# ESP32.net
KiCad netlist of a schematic drawn in Altium Designer
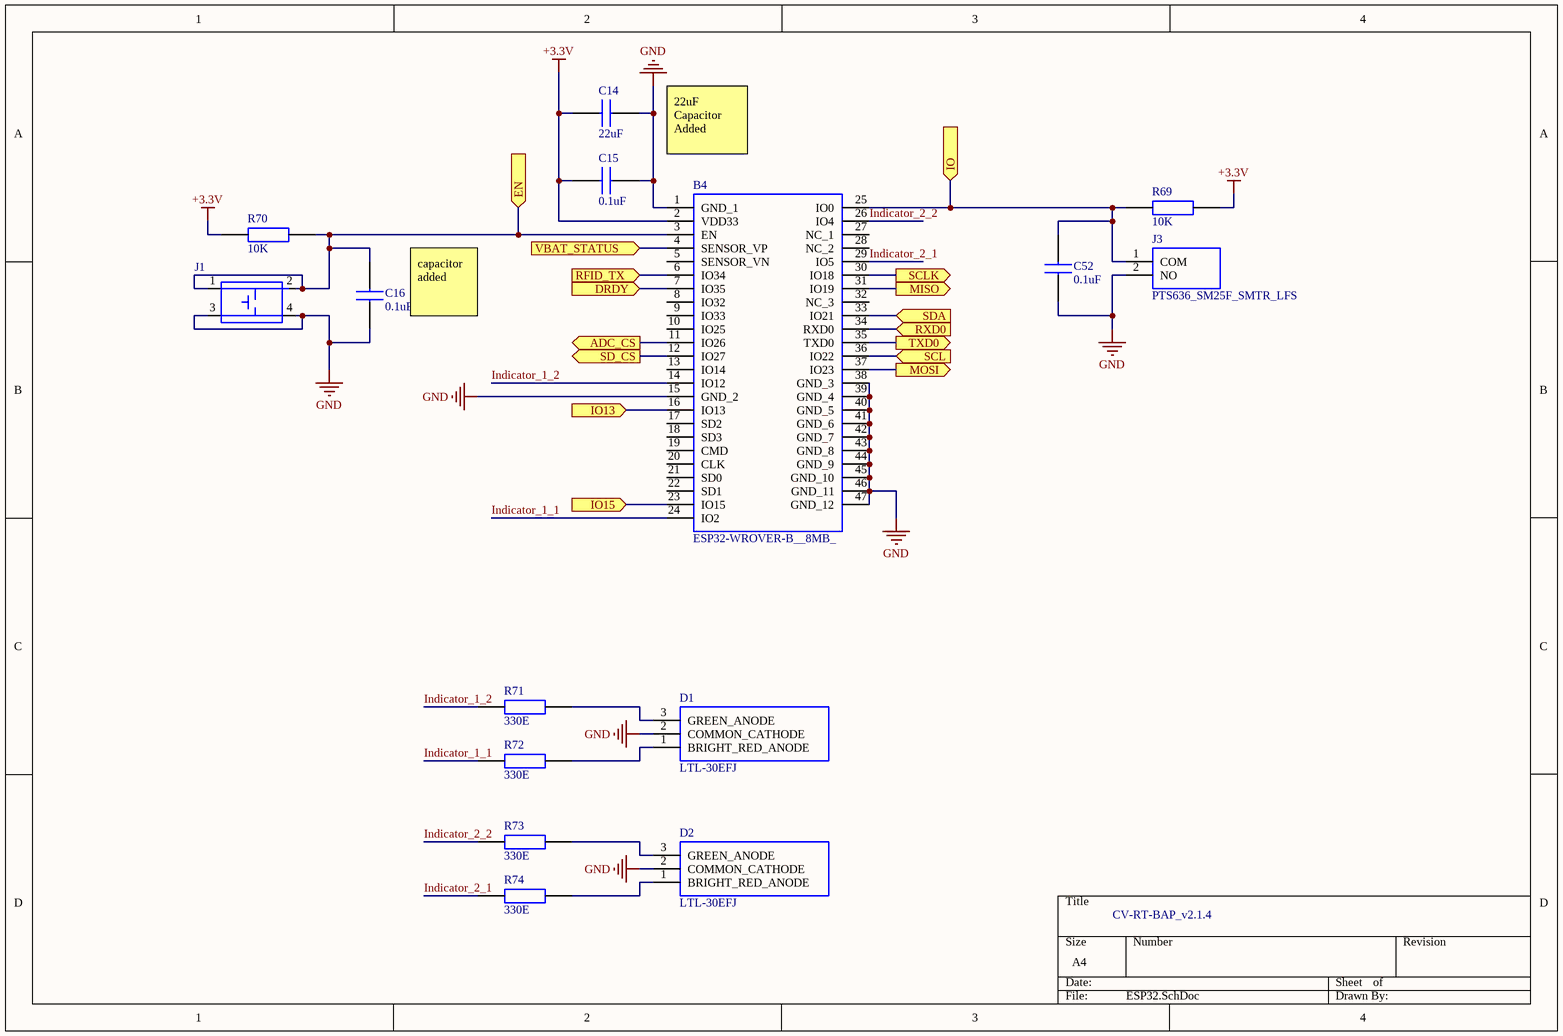
[diagram p0: ESP32.SchDoc]

(export (version "E")
  (design (tool "Eeschema 10.0.6"))
  (components
    (comp (ref "B4")
      (value "ESP32-WROVER-B__8MB_")
      (footprint "ESP32WROVERB8MB")
      (fields
        (field (name "MANUFACTURER_PART_NUMBER") "ESP32-WROVER-B (8MB)")
        (field (name "MOUSER PART NUMBER") "356-ESP32-WRO-B(8MB)")
      )
      (libsource (lib "ESP32-WROVER-B") (part "ESP32-WROVER-B__8MB_"))
    )
    (comp (ref "C14")
      (value "22uF")
      (footprint "CAPC3216X180N")
      (description "Multilayer Ceramic Capacitors MLCC - SMD/SMT 25V 22uF X7R 0402 20%")
      (fields
        (field (name "MANUFACTURER_PART_NUMBER") "C0402C104M4RECTU")
        (field (name "MOUSER PART NUMBER") "80-C0402C104M4RECTU")
      )
      (libsource (lib "0.1uF_0402") (part "C0402C104M4RECTU"))
    )
    (comp (ref "C15")
      (value "0.1uF")
      (footprint "CAPC1005X55N")
      (description "Multilayer Ceramic Capacitors MLCC - SMD/SMT 16V 0.1uF X7R 0402 20%")
      (fields
        (field (name "MANUFACTURER_PART_NUMBER") "C0402C104M4RECTU")
        (field (name "MOUSER PART NUMBER") "80-C0402C104M4RECTU")
      )
      (libsource (lib "0.1uF_0402") (part "C0402C104M4RECTU"))
    )
    (comp (ref "C16")
      (value "0.1uF")
      (footprint "CAPC1005X55N")
      (description "Multilayer Ceramic Capacitors MLCC - SMD/SMT 16V 0.1uF X7R 0402 20%")
      (fields
        (field (name "MANUFACTURER_PART_NUMBER") "C0402C104M4RECTU")
        (field (name "MOUSER PART NUMBER") "80-C0402C104M4RECTU")
      )
      (libsource (lib "0.1uF_0402") (part "C0402C104M4RECTU"))
    )
    (comp (ref "C52")
      (value "0.1uF")
      (footprint "CAPC1005X55N")
      (description "Multilayer Ceramic Capacitors MLCC - SMD/SMT 16V 0.1uF X7R 0402 20%")
      (fields
        (field (name "MANUFACTURER_PART_NUMBER") "C0402C104M4RECTU")
        (field (name "MOUSER PART NUMBER") "80-C0402C104M4RECTU")
      )
      (libsource (lib "0.1uF_0402") (part "C0402C104M4RECTU"))
    )
    (comp (ref "D1")
      (value "LTL-30EFJ")
      (footprint "LTL-30EHJ")
      (description "Standard LEDs - Through Hole Red/Green Diffused")
      (fields (field (name "MOUSER PART NUMBER") "859-LTL-30EFJ"))
      (libsource (lib "5mm_Bi-color") (part "LTL-30EFJ"))
    )
    (comp (ref "D2")
      (value "LTL-30EFJ")
      (footprint "LTL-30EHJ")
      (description "Standard LEDs - Through Hole Red/Green Diffused")
      (fields (field (name "MOUSER PART NUMBER") "859-LTL-30EFJ"))
      (libsource (lib "5mm_Bi-color") (part "LTL-30EFJ"))
    )
    (comp (ref "J1")
      (value "Tactile switch_TH")
      (footprint "Tactile switch_vertical")
      (fields (field (name "PART NUMBER") "SKHHANA010"))
      (libsource (lib "CV-R-BAP_V2.1.5") (part "Tactile switch_TH"))
    )
    (comp (ref "J3")
      (value "PTS636_SM25F_SMTR_LFS")
      (footprint "PTS636SM25FSMTRLFS")
      (description "Tactile Switches Tact 50mA 12VDC, 6.0x3.5, 2.5mm H, 180gf, F leads, No ground pin, White Actuator")
      (fields
        (field (name "MANUFACTURER_PART_NUMBER") "PTS636 SM25F SMTR LFS")
        (field (name "MOUSER PART NUMBER") "611-PTS636SM25FSMTRL")
      )
      (libsource (lib "PTS636") (part "PTS636_SM25F_SMTR_LFS"))
    )
    (comp (ref "R69")
      (value "10K")
      (footprint "RESC1005X40N")
      (fields
        (field (name "MANUFACTURER_PART_NUMBER") "CRCW040210K0FKED")
        (field (name "MOUSER PART NUMBER") "71-CRCW0402-10K-E3")
      )
      (libsource (lib "10K_0402") (part "CRCW040210K0FKED"))
    )
    (comp (ref "R70")
      (value "10K")
      (footprint "RESC1005X40N")
      (fields
        (field (name "MANUFACTURER_PART_NUMBER") "CRCW040210K0FKED")
        (field (name "MOUSER PART NUMBER") "71-CRCW0402-10K-E3")
      )
      (libsource (lib "10K_0402") (part "CRCW040210K0FKED"))
    )
    (comp (ref "R71")
      (value "330E")
      (footprint "RESC1005X40N")
      (description "YAGEO (PHYCOMP) - RC0402FR-07330RL - RES, THICK FILM, 330R, 1%, 0.063W, 0402")
      (fields
        (field (name "MANUFACTURER_PART_NUMBER") "RC0402FR-07330RL")
        (field (name "MOUSER PART NUMBER") "603-RC0402FR-07330RL")
      )
      (libsource (lib "330E_0402") (part "RC0402FR-07330RL"))
    )
    (comp (ref "R72")
      (value "330E")
      (footprint "RESC1005X40N")
      (description "YAGEO (PHYCOMP) - RC0402FR-07330RL - RES, THICK FILM, 330R, 1%, 0.063W, 0402")
      (fields
        (field (name "MANUFACTURER_PART_NUMBER") "RC0402FR-07330RL")
        (field (name "MOUSER PART NUMBER") "603-RC0402FR-07330RL")
      )
      (libsource (lib "330E_0402") (part "RC0402FR-07330RL"))
    )
    (comp (ref "R73")
      (value "330E")
      (footprint "RESC1005X40N")
      (description "YAGEO (PHYCOMP) - RC0402FR-07330RL - RES, THICK FILM, 330R, 1%, 0.063W, 0402")
      (fields
        (field (name "MANUFACTURER_PART_NUMBER") "RC0402FR-07330RL")
        (field (name "MOUSER PART NUMBER") "603-RC0402FR-07330RL")
      )
      (libsource (lib "330E_0402") (part "RC0402FR-07330RL"))
    )
    (comp (ref "R74")
      (value "330E")
      (footprint "RESC1005X40N")
      (description "YAGEO (PHYCOMP) - RC0402FR-07330RL - RES, THICK FILM, 330R, 1%, 0.063W, 0402")
      (fields
        (field (name "MANUFACTURER_PART_NUMBER") "RC0402FR-07330RL")
        (field (name "MOUSER PART NUMBER") "603-RC0402FR-07330RL")
      )
      (libsource (lib "330E_0402") (part "RC0402FR-07330RL"))
    )
  )
  (nets
    (net (code "1") (name "+3.3V") (class "Default")
      (node (ref "B4") (pin "2") (pinfunction "VDD33_2") (pintype "passive"))
      (node (ref "C14") (pin "1") (pinfunction "1_1") (pintype "passive"))
      (node (ref "C15") (pin "1") (pinfunction "1_1") (pintype "passive"))
      (node (ref "R69") (pin "2") (pinfunction "2_2") (pintype "passive"))
      (node (ref "R70") (pin "1") (pinfunction "1_1") (pintype "passive"))
    )
    (net (code "2") (name "/ADC_CS") (class "Default")
      (node (ref "B4") (pin "11") (pinfunction "IO26_11") (pintype "passive"))
    )
    (net (code "3") (name "/DRDY") (class "Default")
      (node (ref "B4") (pin "7") (pinfunction "IO35_7") (pintype "passive"))
    )
    (net (code "4") (name "/EN") (class "Default")
      (node (ref "B4") (pin "3") (pinfunction "EN_3") (pintype "passive"))
      (node (ref "C16") (pin "2") (pinfunction "2_2") (pintype "passive"))
      (node (ref "J1") (pin "1") (pinfunction "1_1") (pintype "passive"))
      (node (ref "J1") (pin "2") (pinfunction "2_2") (pintype "passive"))
      (node (ref "R70") (pin "2") (pinfunction "2_2") (pintype "passive"))
    )
    (net (code "5") (name "/IO") (class "Default")
      (node (ref "B4") (pin "25") (pinfunction "IO0_25") (pintype "passive"))
      (node (ref "C52") (pin "2") (pinfunction "2_2") (pintype "passive"))
      (node (ref "J3") (pin "1") (pinfunction "COM_1") (pintype "passive"))
      (node (ref "R69") (pin "1") (pinfunction "1_1") (pintype "passive"))
    )
    (net (code "6") (name "/IO13") (class "Default")
      (node (ref "B4") (pin "16") (pinfunction "IO13_16") (pintype "passive"))
    )
    (net (code "7") (name "/IO15") (class "Default")
      (node (ref "B4") (pin "23") (pinfunction "IO15_23") (pintype "passive"))
    )
    (net (code "8") (name "/Indicator_1_1") (class "Default")
      (node (ref "B4") (pin "24") (pinfunction "IO2_24") (pintype "passive"))
      (node (ref "R72") (pin "1") (pinfunction "1_1") (pintype "passive"))
    )
    (net (code "9") (name "/Indicator_1_2") (class "Default")
      (node (ref "B4") (pin "14") (pinfunction "IO12_14") (pintype "passive"))
      (node (ref "R71") (pin "1") (pinfunction "1_1") (pintype "passive"))
    )
    (net (code "10") (name "/Indicator_2_1") (class "Default")
      (node (ref "B4") (pin "29") (pinfunction "IO5_29") (pintype "passive"))
      (node (ref "R74") (pin "1") (pinfunction "1_1") (pintype "passive"))
    )
    (net (code "11") (name "/Indicator_2_2") (class "Default")
      (node (ref "B4") (pin "26") (pinfunction "IO4_26") (pintype "passive"))
      (node (ref "R73") (pin "1") (pinfunction "1_1") (pintype "passive"))
    )
    (net (code "12") (name "/MISO") (class "Default")
      (node (ref "B4") (pin "31") (pinfunction "IO19_31") (pintype "passive"))
    )
    (net (code "13") (name "/MOSI") (class "Default")
      (node (ref "B4") (pin "37") (pinfunction "IO23_37") (pintype "passive"))
    )
    (net (code "14") (name "/RFID_TX") (class "Default")
      (node (ref "B4") (pin "6") (pinfunction "IO34_6") (pintype "passive"))
    )
    (net (code "15") (name "/RXD0") (class "Default")
      (node (ref "B4") (pin "34") (pinfunction "RXD0_34") (pintype "passive"))
    )
    (net (code "16") (name "/SCL") (class "Default")
      (node (ref "B4") (pin "36") (pinfunction "IO22_36") (pintype "passive"))
    )
    (net (code "17") (name "/SCLK") (class "Default")
      (node (ref "B4") (pin "30") (pinfunction "IO18_30") (pintype "passive"))
    )
    (net (code "18") (name "/SDA") (class "Default")
      (node (ref "B4") (pin "33") (pinfunction "IO21_33") (pintype "passive"))
    )
    (net (code "19") (name "/SD_CS") (class "Default")
      (node (ref "B4") (pin "12") (pinfunction "IO27_12") (pintype "passive"))
    )
    (net (code "20") (name "/TXD0") (class "Default")
      (node (ref "B4") (pin "35") (pinfunction "TXD0_35") (pintype "passive"))
    )
    (net (code "21") (name "/VBAT_STATUS") (class "Default")
      (node (ref "B4") (pin "4") (pinfunction "SENSOR_VP_4") (pintype "passive"))
    )
    (net (code "22") (name "GND") (class "Default")
      (node (ref "B4") (pin "1") (pinfunction "GND_1_1") (pintype "passive"))
      (node (ref "B4") (pin "15") (pinfunction "GND_2_15") (pintype "passive"))
      (node (ref "B4") (pin "38") (pinfunction "GND_3_38") (pintype "passive"))
      (node (ref "B4") (pin "39") (pinfunction "GND_4_39") (pintype "passive"))
      (node (ref "B4") (pin "40") (pinfunction "GND_5_40") (pintype "passive"))
      (node (ref "B4") (pin "41") (pinfunction "GND_6_41") (pintype "passive"))
      (node (ref "B4") (pin "42") (pinfunction "GND_7_42") (pintype "passive"))
      (node (ref "B4") (pin "43") (pinfunction "GND_8_43") (pintype "passive"))
      (node (ref "B4") (pin "44") (pinfunction "GND_9_44") (pintype "passive"))
      (node (ref "B4") (pin "45") (pinfunction "GND_10_45") (pintype "passive"))
      (node (ref "B4") (pin "46") (pinfunction "GND_11_46") (pintype "passive"))
      (node (ref "B4") (pin "47") (pinfunction "GND_12_47") (pintype "passive"))
      (node (ref "C14") (pin "2") (pinfunction "2_2") (pintype "passive"))
      (node (ref "C15") (pin "2") (pinfunction "2_2") (pintype "passive"))
      (node (ref "C16") (pin "1") (pinfunction "1_1") (pintype "passive"))
      (node (ref "C52") (pin "1") (pinfunction "1_1") (pintype "passive"))
      (node (ref "D1") (pin "2") (pinfunction "COMMON_CATHODE_2") (pintype "passive"))
      (node (ref "D2") (pin "2") (pinfunction "COMMON_CATHODE_2") (pintype "passive"))
      (node (ref "J1") (pin "3") (pinfunction "3_3") (pintype "passive"))
      (node (ref "J1") (pin "4") (pinfunction "4_4") (pintype "passive"))
      (node (ref "J3") (pin "2") (pinfunction "NO_2") (pintype "passive"))
    )
    (net (code "23") (name "Net-(D1-BRIGHT_RED_ANODE)") (class "Default")
      (node (ref "D1") (pin "1") (pinfunction "BRIGHT_RED_ANODE_1") (pintype "passive"))
      (node (ref "R72") (pin "2") (pinfunction "2_2") (pintype "passive"))
    )
    (net (code "24") (name "Net-(D1-GREEN_ANODE)") (class "Default")
      (node (ref "D1") (pin "3") (pinfunction "GREEN_ANODE_3") (pintype "passive"))
      (node (ref "R71") (pin "2") (pinfunction "2_2") (pintype "passive"))
    )
    (net (code "25") (name "Net-(D2-BRIGHT_RED_ANODE)") (class "Default")
      (node (ref "D2") (pin "1") (pinfunction "BRIGHT_RED_ANODE_1") (pintype "passive"))
      (node (ref "R74") (pin "2") (pinfunction "2_2") (pintype "passive"))
    )
    (net (code "26") (name "Net-(D2-GREEN_ANODE)") (class "Default")
      (node (ref "D2") (pin "3") (pinfunction "GREEN_ANODE_3") (pintype "passive"))
      (node (ref "R73") (pin "2") (pinfunction "2_2") (pintype "passive"))
    )
    (net (code "27") (name "unconnected-(B4-CLK-Pad20)") (class "Default")
      (node (ref "B4") (pin "20") (pinfunction "CLK_20") (pintype "passive"))
    )
    (net (code "28") (name "unconnected-(B4-CMD-Pad19)") (class "Default")
      (node (ref "B4") (pin "19") (pinfunction "CMD_19") (pintype "passive"))
    )
    (net (code "29") (name "unconnected-(B4-IO14-Pad13)") (class "Default")
      (node (ref "B4") (pin "13") (pinfunction "IO14_13") (pintype "passive"))
    )
    (net (code "30") (name "unconnected-(B4-IO25-Pad10)") (class "Default")
      (node (ref "B4") (pin "10") (pinfunction "IO25_10") (pintype "passive"))
    )
    (net (code "31") (name "unconnected-(B4-IO32-Pad8)") (class "Default")
      (node (ref "B4") (pin "8") (pinfunction "IO32_8") (pintype "passive"))
    )
    (net (code "32") (name "unconnected-(B4-IO33-Pad9)") (class "Default")
      (node (ref "B4") (pin "9") (pinfunction "IO33_9") (pintype "passive"))
    )
    (net (code "33") (name "unconnected-(B4-NC_1-Pad27)") (class "Default")
      (node (ref "B4") (pin "27") (pinfunction "NC_1_27") (pintype "passive"))
    )
    (net (code "34") (name "unconnected-(B4-NC_2-Pad28)") (class "Default")
      (node (ref "B4") (pin "28") (pinfunction "NC_2_28") (pintype "passive"))
    )
    (net (code "35") (name "unconnected-(B4-NC_3-Pad32)") (class "Default")
      (node (ref "B4") (pin "32") (pinfunction "NC_3_32") (pintype "passive"))
    )
    (net (code "36") (name "unconnected-(B4-SD0-Pad21)") (class "Default")
      (node (ref "B4") (pin "21") (pinfunction "SD0_21") (pintype "passive"))
    )
    (net (code "37") (name "unconnected-(B4-SD1-Pad22)") (class "Default")
      (node (ref "B4") (pin "22") (pinfunction "SD1_22") (pintype "passive"))
    )
    (net (code "38") (name "unconnected-(B4-SD2-Pad17)") (class "Default")
      (node (ref "B4") (pin "17") (pinfunction "SD2_17") (pintype "passive"))
    )
    (net (code "39") (name "unconnected-(B4-SD3-Pad18)") (class "Default")
      (node (ref "B4") (pin "18") (pinfunction "SD3_18") (pintype "passive"))
    )
    (net (code "40") (name "unconnected-(B4-SENSOR_VN-Pad5)") (class "Default")
      (node (ref "B4") (pin "5") (pinfunction "SENSOR_VN_5") (pintype "passive"))
    )
  )
)
